# RFM232_V03.net
KiCad netlist of a schematic drawn in Altium Designer
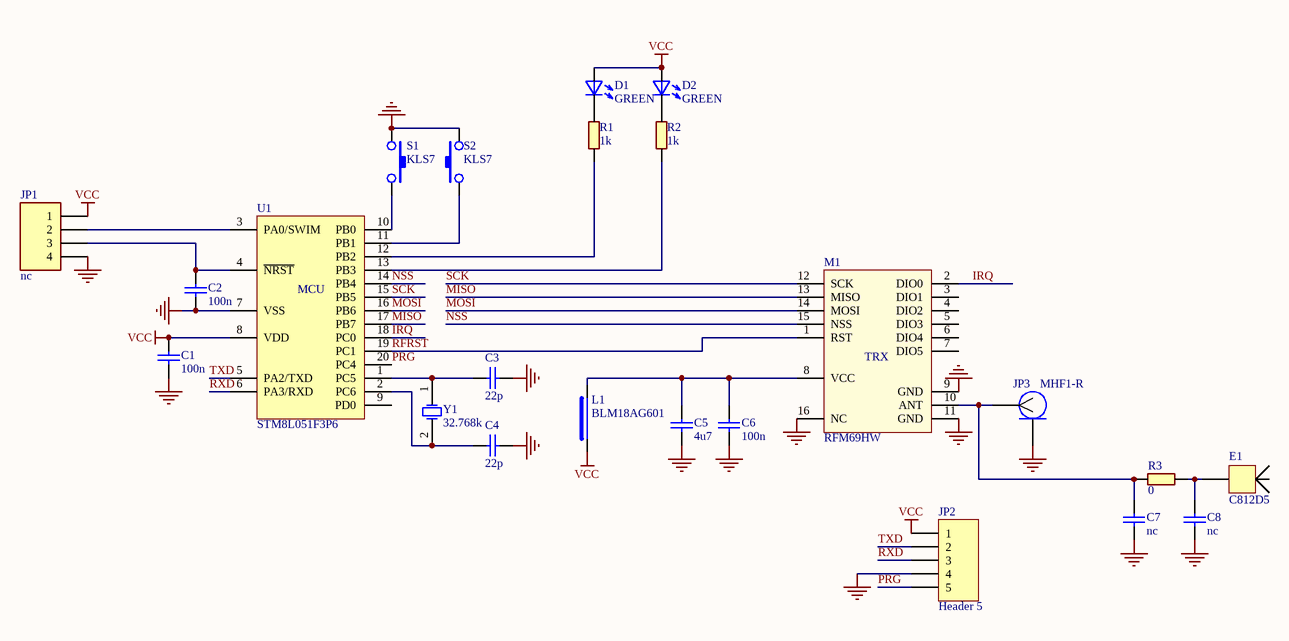
[diagram p0: RFM232_V03.SchDoc]

(export (version "E")
  (design (tool "Eeschema 10.0.6"))
  (components
    (comp (ref "C1") (value "100n") (footprint "CAPC1608X08N") (libsource (lib "Discrete") (part "CAPN")))
    (comp (ref "C2") (value "100n") (footprint "CAPC1608X08N") (libsource (lib "Discrete") (part "CAPN")))
    (comp (ref "C3") (value "22p") (footprint "CAPC1608X08N") (libsource (lib "Discrete") (part "CAPN")))
    (comp (ref "C4") (value "22p") (footprint "CAPC1608X08N") (libsource (lib "Discrete") (part "CAPN")))
    (comp (ref "C5") (value "4u7") (footprint "CAPC2012X11N") (libsource (lib "Discrete") (part "CAPN")))
    (comp (ref "C6") (value "100n") (footprint "CAPC1608X08N") (libsource (lib "Discrete") (part "CAPN")))
    (comp (ref "C7") (value "nc") (footprint "CAPC1608X08N") (libsource (lib "Discrete") (part "CAPN")))
    (comp (ref "C8") (value "nc") (footprint "CAPC1608X08N") (libsource (lib "Discrete") (part "CAPN")))
    (comp (ref "D1")
      (value "GREEN")
      (footprint "LEDC200X125X80L40N")
      (libsource (lib "Discrete") (part "DLED"))
    )
    (comp (ref "D2")
      (value "GREEN")
      (footprint "LEDC200X125X80L40N")
      (libsource (lib "Discrete") (part "DLED"))
    )
    (comp (ref "E1") (value "C812D5") (footprint "C812D5") (libsource (lib "RFUART") (part "C812D5")))
    (comp (ref "JP1")
      (value "nc")
      (footprint "HDRV4W70P254_4X1_889X254H754")
      (description "4 Pin Header 2,0 mm, 1x04")
      (libsource (lib "e4") (part "HEADER 4"))
    )
    (comp (ref "JP2")
      (value "Header 5")
      (footprint "HDRV5W70P254_5X1_1143X254H754")
      (description "Header, 5-Pin")
      (fields (field (name "PUBLISHER") "Altium Limited"))
      (libsource (lib "Miscellaneous Connectors") (part "Header 5"))
    )
    (comp (ref "JP3") (value "MHF1-R") (footprint "MHF1_R") (libsource (lib "RFUART") (part "MHF1")))
    (comp (ref "L1")
      (value "BLM18AG601")
      (footprint "INDC1608X10N")
      (libsource (lib "Discrete") (part "SUPRESOR"))
    )
    (comp (ref "M1")
      (value "RFM69HW")
      (footprint "LGA16_RFM69")
      (libsource (lib "CLAP_M505_WL_BP_V22") (part "RFM69HW_V13_2"))
    )
    (comp (ref "R1") (value "1k") (footprint "RESC1608X06N") (libsource (lib "") (part "RES_1")))
    (comp (ref "R2") (value "1k") (footprint "RESC1608X06N") (libsource (lib "") (part "RES_1")))
    (comp (ref "R3") (value "0") (footprint "RESC1608X06N") (libsource (lib "Discrete") (part "RES")))
    (comp (ref "S1") (value "KLS7") (footprint "KLS7-TS3602") (libsource (lib "CLAP DM-WL-R2") (part "SW-1")))
    (comp (ref "S2") (value "KLS7") (footprint "KLS7-TS3602") (libsource (lib "CLAP DM-WL-R2") (part "SW-1")))
    (comp (ref "U1")
      (value "STM8L051F3P6")
      (footprint "TSOP65P640X110-20N")
      (libsource (lib "reedswitch_stm8l") (part "STM8L051F3P6"))
    )
    (comp (ref "Y1")
      (value "32.768k")
      (footprint "KX26")
      (description "Crystal Oscillator")
      (fields (field (name "PUBLISHER") "Altium Limited"))
      (libsource (lib "Miscellaneous Devices") (part "XTAL"))
    )
  )
  (nets
    (net (code "1") (name "/IRQ") (class "Default")
      (node (ref "M1") (pin "2") (pinfunction "DIO0_2") (pintype "passive"))
      (node (ref "U1") (pin "18") (pinfunction "PC0_18") (pintype "passive"))
    )
    (net (code "2") (name "/MISO") (class "Default")
      (node (ref "M1") (pin "13") (pinfunction "MISO_13") (pintype "passive"))
      (node (ref "U1") (pin "17") (pinfunction "PB7_17") (pintype "passive"))
    )
    (net (code "3") (name "/MOSI") (class "Default")
      (node (ref "M1") (pin "14") (pinfunction "MOSI_14") (pintype "passive"))
      (node (ref "U1") (pin "16") (pinfunction "PB6_16") (pintype "passive"))
    )
    (net (code "4") (name "/NSS") (class "Default")
      (node (ref "M1") (pin "15") (pinfunction "NSS_15") (pintype "passive"))
      (node (ref "U1") (pin "14") (pinfunction "PB4_14") (pintype "passive"))
    )
    (net (code "5") (name "/PRG") (class "Default")
      (node (ref "JP2") (pin "5") (pinfunction "5_5") (pintype "passive"))
      (node (ref "U1") (pin "20") (pinfunction "PC4_20") (pintype "passive"))
    )
    (net (code "6") (name "/RFRST") (class "Default")
      (node (ref "M1") (pin "1") (pinfunction "RST_1") (pintype "passive"))
      (node (ref "U1") (pin "19") (pinfunction "PC1_19") (pintype "passive"))
    )
    (net (code "7") (name "/RXD") (class "Default")
      (node (ref "JP2") (pin "3") (pinfunction "3_3") (pintype "passive"))
      (node (ref "U1") (pin "6") (pinfunction "PA3/RXD_6") (pintype "passive"))
    )
    (net (code "8") (name "/SCK") (class "Default")
      (node (ref "M1") (pin "12") (pinfunction "SCK_12") (pintype "passive"))
      (node (ref "U1") (pin "15") (pinfunction "PB5_15") (pintype "passive"))
    )
    (net (code "9") (name "/TXD") (class "Default")
      (node (ref "JP2") (pin "2") (pinfunction "2_2") (pintype "passive"))
      (node (ref "U1") (pin "5") (pinfunction "PA2/TXD_5") (pintype "passive"))
    )
    (net (code "10") (name "GND") (class "Default")
      (node (ref "C1") (pin "2") (pinfunction "2_2") (pintype "passive"))
      (node (ref "C2") (pin "2") (pinfunction "2_2") (pintype "passive"))
      (node (ref "C3") (pin "2") (pinfunction "2_2") (pintype "passive"))
      (node (ref "C4") (pin "2") (pinfunction "2_2") (pintype "passive"))
      (node (ref "C5") (pin "2") (pinfunction "2_2") (pintype "passive"))
      (node (ref "C6") (pin "2") (pinfunction "2_2") (pintype "passive"))
      (node (ref "C7") (pin "2") (pinfunction "2_2") (pintype "passive"))
      (node (ref "C8") (pin "2") (pinfunction "2_2") (pintype "passive"))
      (node (ref "JP1") (pin "4") (pinfunction "4_4") (pintype "passive"))
      (node (ref "JP2") (pin "4") (pinfunction "4_4") (pintype "passive"))
      (node (ref "JP3") (pin "2") (pinfunction "2_2") (pintype "passive"))
      (node (ref "M1") (pin "11") (pinfunction "GND_11") (pintype "passive"))
      (node (ref "M1") (pin "16") (pinfunction "NC_16") (pintype "passive"))
      (node (ref "M1") (pin "9") (pinfunction "GND_9") (pintype "passive"))
      (node (ref "S1") (pin "1") (pinfunction "1_1") (pintype "passive"))
      (node (ref "S2") (pin "2") (pinfunction "2_2") (pintype "passive"))
      (node (ref "U1") (pin "7") (pinfunction "VSS_7") (pintype "passive"))
    )
    (net (code "11") (name "Net-(D1-2)") (class "Default")
      (node (ref "D1") (pin "K") (pinfunction "2_K") (pintype "passive"))
      (node (ref "R1") (pin "1") (pinfunction "1_1") (pintype "passive"))
    )
    (net (code "12") (name "Net-(D2-2)") (class "Default")
      (node (ref "D2") (pin "K") (pinfunction "2_K") (pintype "passive"))
      (node (ref "R2") (pin "1") (pinfunction "1_1") (pintype "passive"))
    )
    (net (code "13") (name "Net-(E1-IN)") (class "Default")
      (node (ref "C8") (pin "1") (pinfunction "1_1") (pintype "passive"))
      (node (ref "E1") (pin "1") (pinfunction "IN_1") (pintype "passive"))
      (node (ref "R3") (pin "2") (pinfunction "2_2") (pintype "passive"))
    )
    (net (code "14") (name "Net-(M1-ANT)") (class "Default")
      (node (ref "C7") (pin "1") (pinfunction "1_1") (pintype "passive"))
      (node (ref "JP3") (pin "1") (pinfunction "1_1") (pintype "passive"))
      (node (ref "M1") (pin "10") (pinfunction "ANT_10") (pintype "passive"))
      (node (ref "R3") (pin "1") (pinfunction "1_1") (pintype "passive"))
    )
    (net (code "15") (name "Net-(M1-VCC)") (class "Default")
      (node (ref "C5") (pin "1") (pinfunction "1_1") (pintype "passive"))
      (node (ref "C6") (pin "1") (pinfunction "1_1") (pintype "passive"))
      (node (ref "L1") (pin "2") (pinfunction "2_2") (pintype "passive"))
      (node (ref "M1") (pin "8") (pinfunction "VCC_8") (pintype "passive"))
    )
    (net (code "16") (name "Net-(U1-PA0{slash}SWIM)") (class "Default")
      (node (ref "JP1") (pin "2") (pinfunction "2_2") (pintype "passive"))
      (node (ref "U1") (pin "3") (pinfunction "PA0/SWIM_3") (pintype "passive"))
    )
    (net (code "17") (name "Net-(U1-PB0)") (class "Default")
      (node (ref "S1") (pin "2") (pinfunction "2_2") (pintype "passive"))
      (node (ref "U1") (pin "10") (pinfunction "PB0_10") (pintype "passive"))
    )
    (net (code "18") (name "Net-(U1-PB1)") (class "Default")
      (node (ref "S2") (pin "1") (pinfunction "1_1") (pintype "passive"))
      (node (ref "U1") (pin "11") (pinfunction "PB1_11") (pintype "passive"))
    )
    (net (code "19") (name "Net-(U1-PB2)") (class "Default")
      (node (ref "R1") (pin "2") (pinfunction "2_2") (pintype "passive"))
      (node (ref "U1") (pin "12") (pinfunction "PB2_12") (pintype "passive"))
    )
    (net (code "20") (name "Net-(U1-PB3)") (class "Default")
      (node (ref "R2") (pin "2") (pinfunction "2_2") (pintype "passive"))
      (node (ref "U1") (pin "13") (pinfunction "PB3_13") (pintype "passive"))
    )
    (net (code "21") (name "Net-(U1-PC5)") (class "Default")
      (node (ref "C3") (pin "1") (pinfunction "1_1") (pintype "passive"))
      (node (ref "U1") (pin "1") (pinfunction "PC5_1") (pintype "passive"))
      (node (ref "Y1") (pin "1") (pinfunction "OSC1_1") (pintype "passive"))
    )
    (net (code "22") (name "Net-(U1-PC6)") (class "Default")
      (node (ref "C4") (pin "1") (pinfunction "1_1") (pintype "passive"))
      (node (ref "U1") (pin "2") (pinfunction "PC6_2") (pintype "passive"))
      (node (ref "Y1") (pin "2") (pinfunction "OSC2_2") (pintype "passive"))
    )
    (net (code "23") (name "Net-(U1-~{NRST})") (class "Default")
      (node (ref "C2") (pin "1") (pinfunction "1_1") (pintype "passive"))
      (node (ref "JP1") (pin "3") (pinfunction "3_3") (pintype "passive"))
      (node (ref "U1") (pin "4") (pinfunction "~{NRST}_4") (pintype "passive"))
    )
    (net (code "24") (name "VCC") (class "Default")
      (node (ref "C1") (pin "1") (pinfunction "1_1") (pintype "passive"))
      (node (ref "D1") (pin "A") (pinfunction "1_A") (pintype "passive"))
      (node (ref "D2") (pin "A") (pinfunction "1_A") (pintype "passive"))
      (node (ref "JP1") (pin "1") (pinfunction "1_1") (pintype "passive"))
      (node (ref "JP2") (pin "1") (pinfunction "1_1") (pintype "passive"))
      (node (ref "L1") (pin "1") (pinfunction "1_1") (pintype "passive"))
      (node (ref "U1") (pin "8") (pinfunction "VDD_8") (pintype "passive"))
    )
    (net (code "25") (name "unconnected-(M1-DIO1-Pad3)") (class "Default")
      (node (ref "M1") (pin "3") (pinfunction "DIO1_3") (pintype "passive"))
    )
    (net (code "26") (name "unconnected-(M1-DIO2-Pad4)") (class "Default")
      (node (ref "M1") (pin "4") (pinfunction "DIO2_4") (pintype "passive"))
    )
    (net (code "27") (name "unconnected-(M1-DIO3-Pad5)") (class "Default")
      (node (ref "M1") (pin "5") (pinfunction "DIO3_5") (pintype "passive"))
    )
    (net (code "28") (name "unconnected-(M1-DIO4-Pad6)") (class "Default")
      (node (ref "M1") (pin "6") (pinfunction "DIO4_6") (pintype "passive"))
    )
    (net (code "29") (name "unconnected-(M1-DIO5-Pad7)") (class "Default")
      (node (ref "M1") (pin "7") (pinfunction "DIO5_7") (pintype "passive"))
    )
    (net (code "30") (name "unconnected-(U1-PD0-Pad9)") (class "Default")
      (node (ref "U1") (pin "9") (pinfunction "PD0_9") (pintype "passive"))
    )
  )
)
